# CPU_board.net
KiCad netlist of a schematic drawn in EAGLE
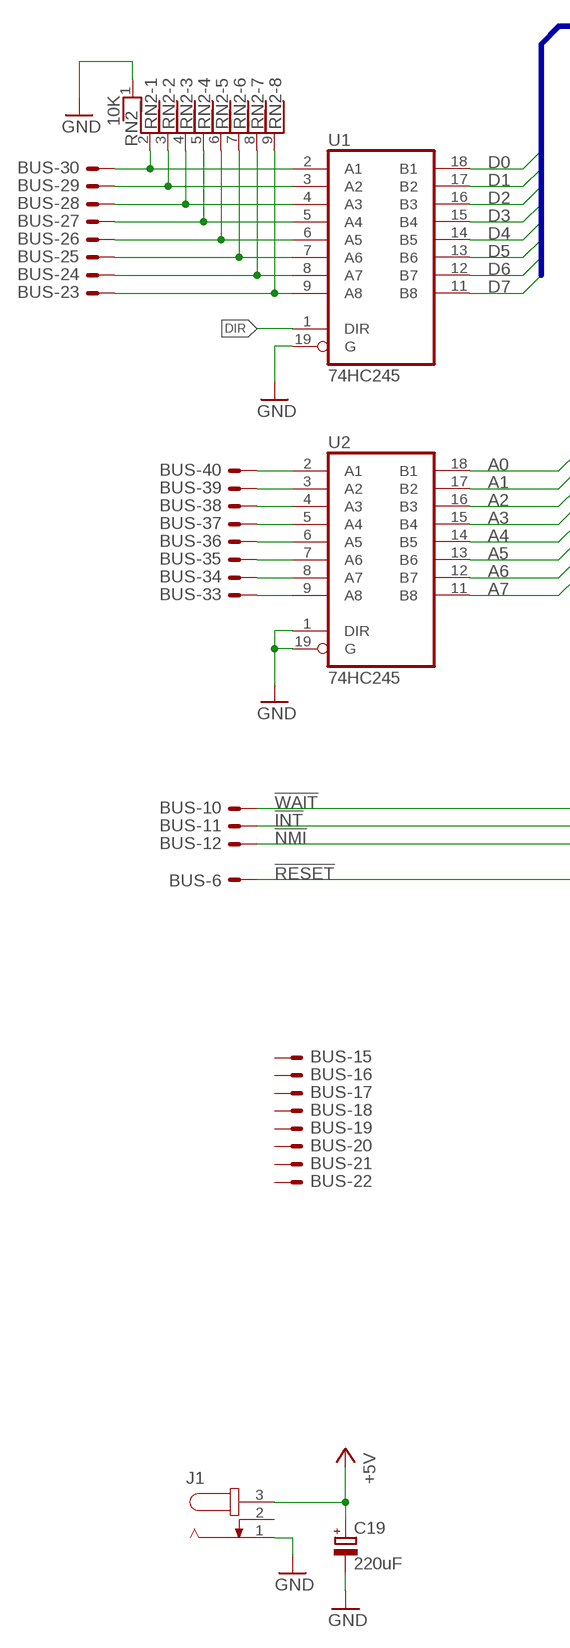
[diagram p0: schematic, sheet 1, part 1 of 2]
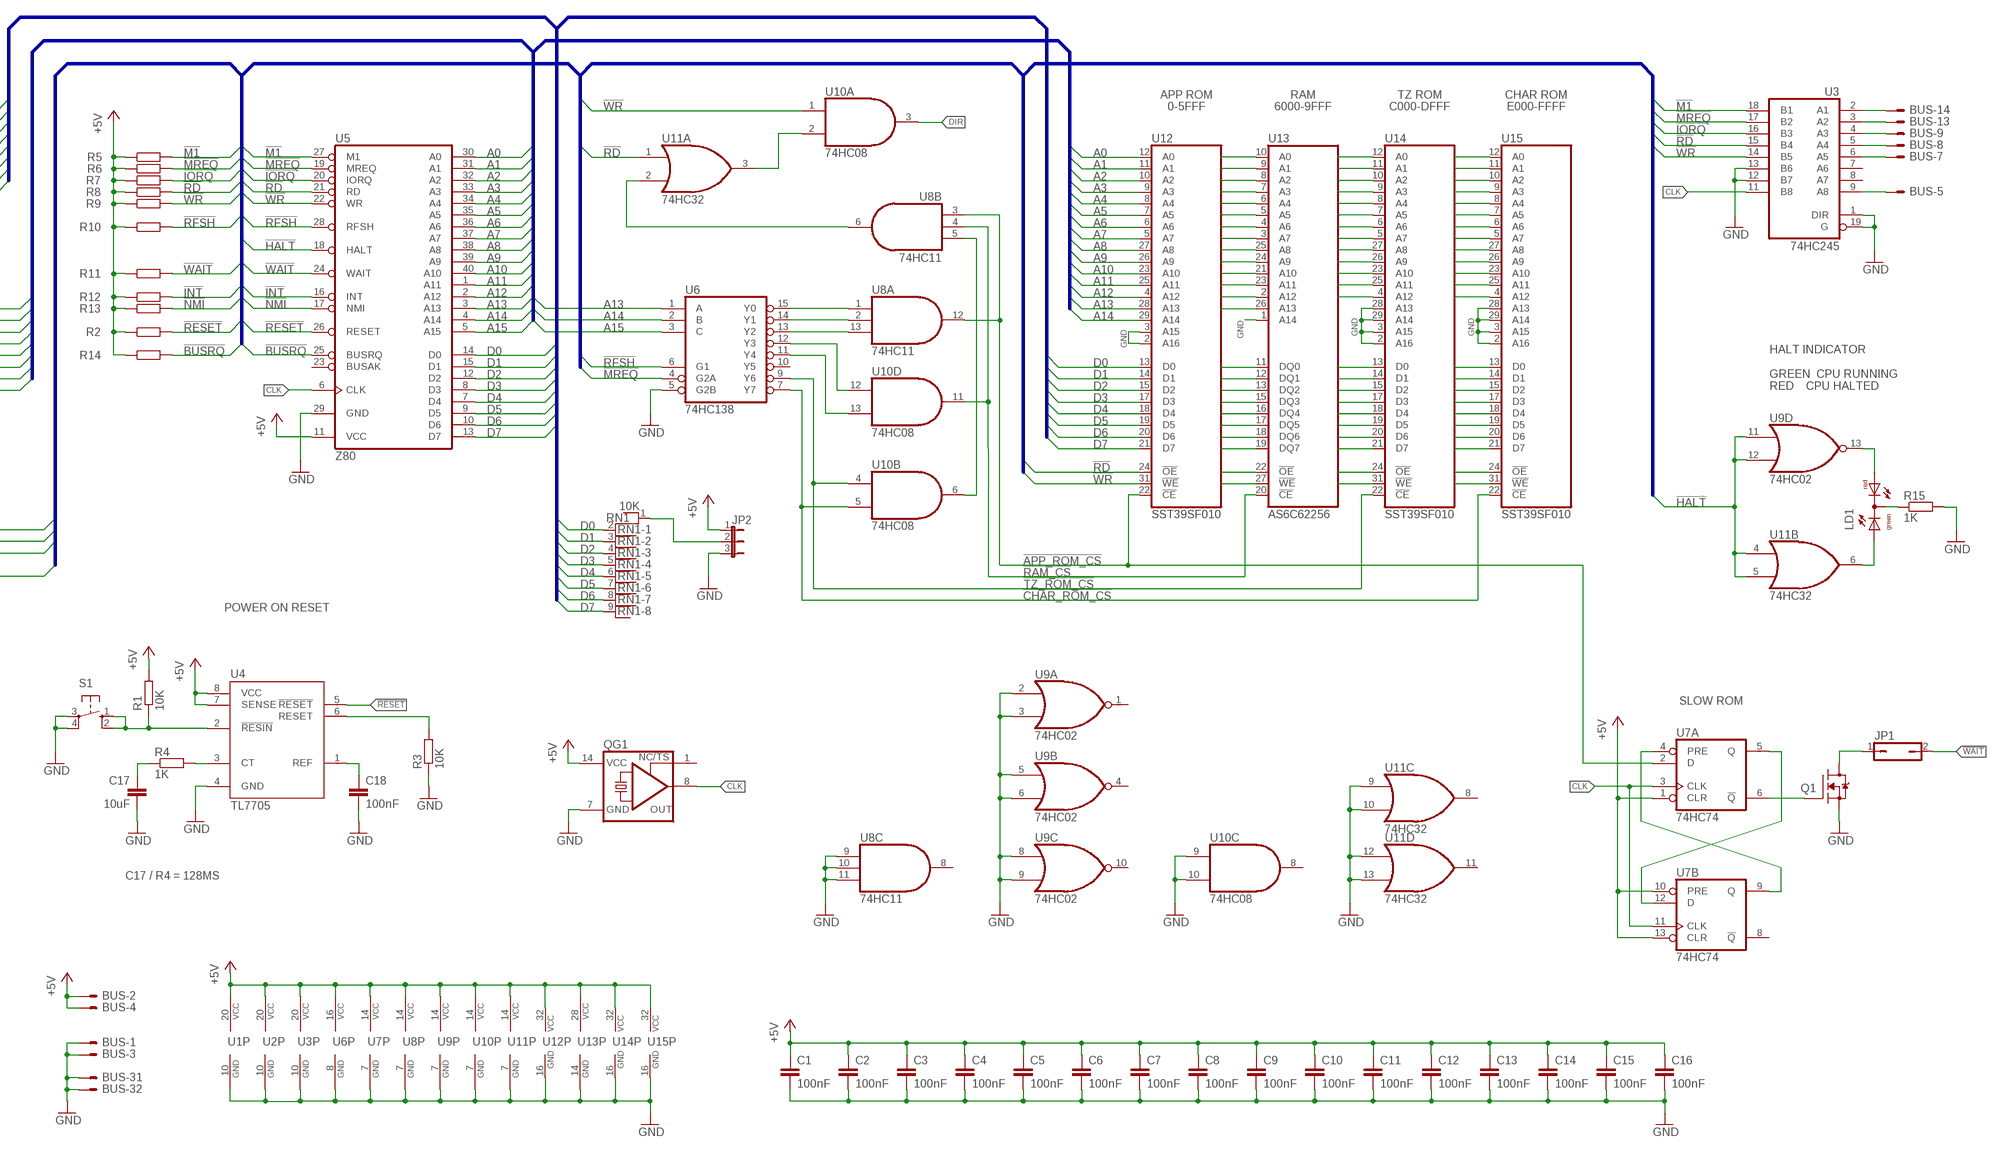
[diagram p1: schematic, sheet 1, part 2 of 2]

(export (version "E")
  (design (tool "Eeschema 10.0.6"))
  (components
    (comp (ref "BUS")
      (value "ML40E")
      (footprint "eagle-import:ML40")
      (libsource (lib "eagle-import") (part "ML40E"))
    )
    (comp (ref "C1")
      (value "100nF")
      (footprint "eagle-import:C050-025X075")
      (libsource (lib "eagle-import") (part "C-EU050-025X075"))
    )
    (comp (ref "C2")
      (value "100nF")
      (footprint "eagle-import:C050-025X075")
      (libsource (lib "eagle-import") (part "C-EU050-025X075"))
    )
    (comp (ref "C3")
      (value "100nF")
      (footprint "eagle-import:C050-025X075")
      (libsource (lib "eagle-import") (part "C-EU050-025X075"))
    )
    (comp (ref "C4")
      (value "100nF")
      (footprint "eagle-import:C050-025X075")
      (libsource (lib "eagle-import") (part "C-EU050-025X075"))
    )
    (comp (ref "C5")
      (value "100nF")
      (footprint "eagle-import:C050-025X075")
      (libsource (lib "eagle-import") (part "C-EU050-025X075"))
    )
    (comp (ref "C6")
      (value "100nF")
      (footprint "eagle-import:C050-025X075")
      (libsource (lib "eagle-import") (part "C-EU050-025X075"))
    )
    (comp (ref "C7")
      (value "100nF")
      (footprint "eagle-import:C050-025X075")
      (libsource (lib "eagle-import") (part "C-EU050-025X075"))
    )
    (comp (ref "C8")
      (value "100nF")
      (footprint "eagle-import:C050-025X075")
      (libsource (lib "eagle-import") (part "C-EU050-025X075"))
    )
    (comp (ref "C9")
      (value "100nF")
      (footprint "eagle-import:C050-025X075")
      (libsource (lib "eagle-import") (part "C-EU050-025X075"))
    )
    (comp (ref "C10")
      (value "100nF")
      (footprint "eagle-import:C050-025X075")
      (libsource (lib "eagle-import") (part "C-EU050-025X075"))
    )
    (comp (ref "C11")
      (value "100nF")
      (footprint "eagle-import:C050-025X075")
      (libsource (lib "eagle-import") (part "C-EU050-025X075"))
    )
    (comp (ref "C12")
      (value "100nF")
      (footprint "eagle-import:C050-025X075")
      (libsource (lib "eagle-import") (part "C-EU050-025X075"))
    )
    (comp (ref "C13")
      (value "100nF")
      (footprint "eagle-import:C050-025X075")
      (libsource (lib "eagle-import") (part "C-EU050-025X075"))
    )
    (comp (ref "C14")
      (value "100nF")
      (footprint "eagle-import:C050-025X075")
      (libsource (lib "eagle-import") (part "C-EU050-025X075"))
    )
    (comp (ref "C15")
      (value "100nF")
      (footprint "eagle-import:C050-025X075")
      (libsource (lib "eagle-import") (part "C-EU050-025X075"))
    )
    (comp (ref "C16")
      (value "100nF")
      (footprint "eagle-import:C050-025X075")
      (libsource (lib "eagle-import") (part "C-EU050-025X075"))
    )
    (comp (ref "C17")
      (value "10uF")
      (footprint "eagle-import:C050-025X075")
      (libsource (lib "eagle-import") (part "C-EU050-025X075"))
    )
    (comp (ref "C18")
      (value "100nF")
      (footprint "eagle-import:C050-025X075")
      (libsource (lib "eagle-import") (part "C-EU050-025X075"))
    )
    (comp (ref "C19")
      (value "220uF")
      (footprint "eagle-import:E3,5-8")
      (libsource (lib "eagle-import") (part "CPOL-EUE3.5-8"))
    )
    (comp (ref "J1")
      (value "JACK-PLUG0")
      (footprint "eagle-import:SPC4077")
      (libsource (lib "eagle-import") (part "JACK-PLUG0"))
    )
    (comp (ref "JP1")
      (value "JP1Q")
      (footprint "eagle-import:JP1")
      (libsource (lib "eagle-import") (part "JP1Q"))
    )
    (comp (ref "JP2")
      (value "JP2E")
      (footprint "eagle-import:JP2")
      (libsource (lib "eagle-import") (part "JP2E"))
    )
    (comp (ref "LD1")
      (value "DUOLED-RG-C")
      (footprint "eagle-import:DUOLED-C-5MM")
      (libsource (lib "eagle-import") (part "DUOLED-RG-C"))
    )
    (comp (ref "Q1")
      (value "2N7000")
      (footprint "eagle-import:TO-92-FORMED")
      (libsource (lib "eagle-import") (part "2N7000"))
    )
    (comp (ref "QG1")
      (value "XO-14")
      (footprint "eagle-import:DIL14S")
      (libsource (lib "eagle-import") (part "XO-14"))
    )
    (comp (ref "R1")
      (value "10K")
      (footprint "eagle-import:0207_10")
      (libsource (lib "eagle-import") (part "R-EU_0207/10"))
    )
    (comp (ref "R2")
      (value "10K")
      (footprint "eagle-import:0207_10")
      (libsource (lib "eagle-import") (part "R-EU_0207/10"))
    )
    (comp (ref "R3")
      (value "10K")
      (footprint "eagle-import:0207_10")
      (libsource (lib "eagle-import") (part "R-EU_0207/10"))
    )
    (comp (ref "R4")
      (value "1K")
      (footprint "eagle-import:0207_10")
      (libsource (lib "eagle-import") (part "R-EU_0207/10"))
    )
    (comp (ref "R5")
      (value "R-EU_0207/10")
      (footprint "eagle-import:0207_10")
      (libsource (lib "eagle-import") (part "R-EU_0207/10"))
    )
    (comp (ref "R6")
      (value "R-EU_0207/10")
      (footprint "eagle-import:0207_10")
      (libsource (lib "eagle-import") (part "R-EU_0207/10"))
    )
    (comp (ref "R7")
      (value "R-EU_0207/10")
      (footprint "eagle-import:0207_10")
      (libsource (lib "eagle-import") (part "R-EU_0207/10"))
    )
    (comp (ref "R8")
      (value "R-EU_0207/10")
      (footprint "eagle-import:0207_10")
      (libsource (lib "eagle-import") (part "R-EU_0207/10"))
    )
    (comp (ref "R9")
      (value "R-EU_0207/10")
      (footprint "eagle-import:0207_10")
      (libsource (lib "eagle-import") (part "R-EU_0207/10"))
    )
    (comp (ref "R10")
      (value "R-EU_0207/10")
      (footprint "eagle-import:0207_10")
      (libsource (lib "eagle-import") (part "R-EU_0207/10"))
    )
    (comp (ref "R11")
      (value "R-EU_0207/10")
      (footprint "eagle-import:0207_10")
      (libsource (lib "eagle-import") (part "R-EU_0207/10"))
    )
    (comp (ref "R12")
      (value "R-EU_0207/10")
      (footprint "eagle-import:0207_10")
      (libsource (lib "eagle-import") (part "R-EU_0207/10"))
    )
    (comp (ref "R13")
      (value "R-EU_0207/10")
      (footprint "eagle-import:0207_10")
      (libsource (lib "eagle-import") (part "R-EU_0207/10"))
    )
    (comp (ref "R14")
      (value "R-EU_0207/10")
      (footprint "eagle-import:0207_10")
      (libsource (lib "eagle-import") (part "R-EU_0207/10"))
    )
    (comp (ref "R15")
      (value "1K")
      (footprint "eagle-import:0207_10")
      (libsource (lib "eagle-import") (part "R-EU_0207/10"))
    )
    (comp (ref "RN1")
      (value "10K")
      (footprint "eagle-import:RN-9")
      (libsource (lib "eagle-import") (part "RNX8"))
    )
    (comp (ref "RN2")
      (value "10K")
      (footprint "eagle-import:RN-9")
      (libsource (lib "eagle-import") (part "RNX8"))
    )
    (comp (ref "S1")
      (value "10-XX")
      (footprint "eagle-import:B3F-10XX")
      (fields (field (name "MPN") "B3F-1000"))
      (libsource (lib "eagle-import") (part "10-XX"))
    )
    (comp (ref "U1")
      (value "74HC245")
      (footprint "eagle-import:DIL20")
      (libsource (lib "eagle-import") (part "74245NLS"))
    )
    (comp (ref "U2")
      (value "74HC245")
      (footprint "eagle-import:DIL20")
      (libsource (lib "eagle-import") (part "74245NLS"))
    )
    (comp (ref "U3")
      (value "74HC245")
      (footprint "eagle-import:DIL20")
      (libsource (lib "eagle-import") (part "74245NLS"))
    )
    (comp (ref "U4")
      (value "TL7705")
      (footprint "eagle-import:DIL08")
      (libsource (lib "eagle-import") (part "TL77XXA"))
    )
    (comp (ref "U5")
      (value "Z80")
      (footprint "eagle-import:DIL40")
      (libsource (lib "eagle-import") (part "Z80CPU"))
    )
    (comp (ref "U6")
      (value "74HC138")
      (footprint "eagle-import:DIL16")
      (libsource (lib "eagle-import") (part "74138NLS"))
    )
    (comp (ref "U7")
      (value "74HC74")
      (footprint "eagle-import:DIL14")
      (libsource (lib "eagle-import") (part "7474NLS"))
    )
    (comp (ref "U8")
      (value "74HC11")
      (footprint "eagle-import:DIL14")
      (libsource (lib "eagle-import") (part "7411NLS"))
    )
    (comp (ref "U9")
      (value "74HC02")
      (footprint "eagle-import:DIL14")
      (libsource (lib "eagle-import") (part "7402NLS"))
    )
    (comp (ref "U10")
      (value "74HC08")
      (footprint "eagle-import:DIL14")
      (libsource (lib "eagle-import") (part "7408NLS"))
    )
    (comp (ref "U11")
      (value "74HC32")
      (footprint "eagle-import:DIL14")
      (libsource (lib "eagle-import") (part "7432NLS"))
    )
    (comp (ref "U12")
      (value "SST39SF010")
      (footprint "eagle-import:DIL32")
      (libsource (lib "eagle-import") (part "SST39SF010P"))
    )
    (comp (ref "U13")
      (value "AS6C62256")
      (footprint "eagle-import:DIL28-6")
      (libsource (lib "eagle-import") (part "AS6C62256-55PCN"))
    )
    (comp (ref "U14")
      (value "SST39SF010")
      (footprint "eagle-import:PLCC-SR32")
      (libsource (lib "eagle-import") (part "SST39SF010NS"))
    )
    (comp (ref "U15")
      (value "SST39SF010")
      (footprint "eagle-import:PLCC-SR32")
      (libsource (lib "eagle-import") (part "SST39SF010NS"))
    )
  )
  (nets
    (net (code "18") (name "+5V") (class "Default")
      (node (ref "BUS") (pin "2") (pinfunction "S_2") (pintype "passive"))
      (node (ref "BUS") (pin "4") (pinfunction "S_4") (pintype "passive"))
      (node (ref "C1") (pin "1") (pinfunction "1_1") (pintype "passive"))
      (node (ref "C10") (pin "1") (pinfunction "1_1") (pintype "passive"))
      (node (ref "C11") (pin "1") (pinfunction "1_1") (pintype "passive"))
      (node (ref "C12") (pin "1") (pinfunction "1_1") (pintype "passive"))
      (node (ref "C13") (pin "1") (pinfunction "1_1") (pintype "passive"))
      (node (ref "C14") (pin "1") (pinfunction "1_1") (pintype "passive"))
      (node (ref "C15") (pin "1") (pinfunction "1_1") (pintype "passive"))
      (node (ref "C16") (pin "1") (pinfunction "1_1") (pintype "passive"))
      (node (ref "C19") (pin "+") (pinfunction "+_+") (pintype "passive"))
      (node (ref "C2") (pin "1") (pinfunction "1_1") (pintype "passive"))
      (node (ref "C3") (pin "1") (pinfunction "1_1") (pintype "passive"))
      (node (ref "C4") (pin "1") (pinfunction "1_1") (pintype "passive"))
      (node (ref "C5") (pin "1") (pinfunction "1_1") (pintype "passive"))
      (node (ref "C6") (pin "1") (pinfunction "1_1") (pintype "passive"))
      (node (ref "C7") (pin "1") (pinfunction "1_1") (pintype "passive"))
      (node (ref "C8") (pin "1") (pinfunction "1_1") (pintype "passive"))
      (node (ref "C9") (pin "1") (pinfunction "1_1") (pintype "passive"))
      (node (ref "J1") (pin "3") (pinfunction "3_3") (pintype "passive"))
      (node (ref "JP2") (pin "1") (pinfunction "1_1") (pintype "passive"))
      (node (ref "QG1") (pin "14") (pinfunction "VCC_14") (pintype "power_in"))
      (node (ref "R1") (pin "2") (pinfunction "2_2") (pintype "passive"))
      (node (ref "R10") (pin "1") (pinfunction "1_1") (pintype "passive"))
      (node (ref "R11") (pin "1") (pinfunction "1_1") (pintype "passive"))
      (node (ref "R12") (pin "1") (pinfunction "1_1") (pintype "passive"))
      (node (ref "R13") (pin "1") (pinfunction "1_1") (pintype "passive"))
      (node (ref "R14") (pin "1") (pinfunction "1_1") (pintype "passive"))
      (node (ref "R2") (pin "1") (pinfunction "1_1") (pintype "passive"))
      (node (ref "R5") (pin "1") (pinfunction "1_1") (pintype "passive"))
      (node (ref "R6") (pin "1") (pinfunction "1_1") (pintype "passive"))
      (node (ref "R7") (pin "1") (pinfunction "1_1") (pintype "passive"))
      (node (ref "R8") (pin "1") (pinfunction "1_1") (pintype "passive"))
      (node (ref "R9") (pin "1") (pinfunction "1_1") (pintype "passive"))
      (node (ref "U1") (pin "20") (pinfunction "VCC_20") (pintype "power_in"))
      (node (ref "U10") (pin "14") (pinfunction "VCC_14") (pintype "power_in"))
      (node (ref "U11") (pin "14") (pinfunction "VCC_14") (pintype "power_in"))
      (node (ref "U12") (pin "32") (pinfunction "VCC_32") (pintype "power_in"))
      (node (ref "U13") (pin "28") (pinfunction "VCC_28") (pintype "power_in"))
      (node (ref "U14") (pin "32") (pinfunction "VCC_32") (pintype "power_in"))
      (node (ref "U15") (pin "32") (pinfunction "VCC_32") (pintype "power_in"))
      (node (ref "U2") (pin "20") (pinfunction "VCC_20") (pintype "power_in"))
      (node (ref "U3") (pin "20") (pinfunction "VCC_20") (pintype "power_in"))
      (node (ref "U4") (pin "7") (pinfunction "SENSE_7") (pintype "input"))
      (node (ref "U4") (pin "8") (pinfunction "VCC_8") (pintype "power_in"))
      (node (ref "U5") (pin "11") (pinfunction "VCC_11") (pintype "power_in"))
      (node (ref "U6") (pin "16") (pinfunction "VCC_16") (pintype "power_in"))
      (node (ref "U7") (pin "1") (pinfunction "CLR_1") (pintype "input"))
      (node (ref "U7") (pin "10") (pinfunction "PRE_10") (pintype "input"))
      (node (ref "U7") (pin "13") (pinfunction "CLR_13") (pintype "input"))
      (node (ref "U7") (pin "14") (pinfunction "VCC_14") (pintype "power_in"))
      (node (ref "U8") (pin "14") (pinfunction "VCC_14") (pintype "power_in"))
      (node (ref "U9") (pin "14") (pinfunction "VCC_14") (pintype "power_in"))
    )
    (net (code "21") (name "A0") (class "Default")
      (node (ref "U12") (pin "12") (pinfunction "A0_12") (pintype "input"))
      (node (ref "U13") (pin "10") (pinfunction "A0_10") (pintype "input"))
      (node (ref "U14") (pin "12") (pinfunction "A0_12") (pintype "input"))
      (node (ref "U15") (pin "12") (pinfunction "A0_12") (pintype "input"))
      (node (ref "U2") (pin "18") (pinfunction "B1_18") (pintype "bidirectional"))
      (node (ref "U5") (pin "30") (pinfunction "A0_30") (pintype "output"))
    )
    (net (code "22") (name "A1") (class "Default")
      (node (ref "U12") (pin "11") (pinfunction "A1_11") (pintype "input"))
      (node (ref "U13") (pin "9") (pinfunction "A1_9") (pintype "input"))
      (node (ref "U14") (pin "11") (pinfunction "A1_11") (pintype "input"))
      (node (ref "U15") (pin "11") (pinfunction "A1_11") (pintype "input"))
      (node (ref "U2") (pin "17") (pinfunction "B2_17") (pintype "bidirectional"))
      (node (ref "U5") (pin "31") (pinfunction "A1_31") (pintype "output"))
    )
    (net (code "23") (name "A2") (class "Default")
      (node (ref "U12") (pin "10") (pinfunction "A2_10") (pintype "input"))
      (node (ref "U13") (pin "8") (pinfunction "A2_8") (pintype "input"))
      (node (ref "U14") (pin "10") (pinfunction "A2_10") (pintype "input"))
      (node (ref "U15") (pin "10") (pinfunction "A2_10") (pintype "input"))
      (node (ref "U2") (pin "16") (pinfunction "B3_16") (pintype "bidirectional"))
      (node (ref "U5") (pin "32") (pinfunction "A2_32") (pintype "output"))
    )
    (net (code "24") (name "A3") (class "Default")
      (node (ref "U12") (pin "9") (pinfunction "A3_9") (pintype "input"))
      (node (ref "U13") (pin "7") (pinfunction "A3_7") (pintype "input"))
      (node (ref "U14") (pin "9") (pinfunction "A3_9") (pintype "input"))
      (node (ref "U15") (pin "9") (pinfunction "A3_9") (pintype "input"))
      (node (ref "U2") (pin "15") (pinfunction "B4_15") (pintype "bidirectional"))
      (node (ref "U5") (pin "33") (pinfunction "A3_33") (pintype "output"))
    )
    (net (code "25") (name "A4") (class "Default")
      (node (ref "U12") (pin "8") (pinfunction "A4_8") (pintype "input"))
      (node (ref "U13") (pin "6") (pinfunction "A4_6") (pintype "input"))
      (node (ref "U14") (pin "8") (pinfunction "A4_8") (pintype "input"))
      (node (ref "U15") (pin "8") (pinfunction "A4_8") (pintype "input"))
      (node (ref "U2") (pin "14") (pinfunction "B5_14") (pintype "bidirectional"))
      (node (ref "U5") (pin "34") (pinfunction "A4_34") (pintype "output"))
    )
    (net (code "26") (name "A5") (class "Default")
      (node (ref "U12") (pin "7") (pinfunction "A5_7") (pintype "input"))
      (node (ref "U13") (pin "5") (pinfunction "A5_5") (pintype "input"))
      (node (ref "U14") (pin "7") (pinfunction "A5_7") (pintype "input"))
      (node (ref "U15") (pin "7") (pinfunction "A5_7") (pintype "input"))
      (node (ref "U2") (pin "13") (pinfunction "B6_13") (pintype "bidirectional"))
      (node (ref "U5") (pin "35") (pinfunction "A5_35") (pintype "output"))
    )
    (net (code "27") (name "A6") (class "Default")
      (node (ref "U12") (pin "6") (pinfunction "A6_6") (pintype "input"))
      (node (ref "U13") (pin "4") (pinfunction "A6_4") (pintype "input"))
      (node (ref "U14") (pin "6") (pinfunction "A6_6") (pintype "input"))
      (node (ref "U15") (pin "6") (pinfunction "A6_6") (pintype "input"))
      (node (ref "U2") (pin "12") (pinfunction "B7_12") (pintype "bidirectional"))
      (node (ref "U5") (pin "36") (pinfunction "A6_36") (pintype "output"))
    )
    (net (code "28") (name "A7") (class "Default")
      (node (ref "U12") (pin "5") (pinfunction "A7_5") (pintype "input"))
      (node (ref "U13") (pin "3") (pinfunction "A7_3") (pintype "input"))
      (node (ref "U14") (pin "5") (pinfunction "A7_5") (pintype "input"))
      (node (ref "U15") (pin "5") (pinfunction "A7_5") (pintype "input"))
      (node (ref "U2") (pin "11") (pinfunction "B8_11") (pintype "bidirectional"))
      (node (ref "U5") (pin "37") (pinfunction "A7_37") (pintype "output"))
    )
    (net (code "29") (name "A8") (class "Default")
      (node (ref "U12") (pin "27") (pinfunction "A8_27") (pintype "input"))
      (node (ref "U13") (pin "25") (pinfunction "A8_25") (pintype "input"))
      (node (ref "U14") (pin "27") (pinfunction "A8_27") (pintype "input"))
      (node (ref "U15") (pin "27") (pinfunction "A8_27") (pintype "input"))
      (node (ref "U5") (pin "38") (pinfunction "A8_38") (pintype "output"))
    )
    (net (code "30") (name "A9") (class "Default")
      (node (ref "U12") (pin "26") (pinfunction "A9_26") (pintype "input"))
      (node (ref "U13") (pin "24") (pinfunction "A9_24") (pintype "input"))
      (node (ref "U14") (pin "26") (pinfunction "A9_26") (pintype "input"))
      (node (ref "U15") (pin "26") (pinfunction "A9_26") (pintype "input"))
      (node (ref "U5") (pin "39") (pinfunction "A9_39") (pintype "output"))
    )
    (net (code "31") (name "A10") (class "Default")
      (node (ref "U12") (pin "23") (pinfunction "A10_23") (pintype "input"))
      (node (ref "U13") (pin "21") (pinfunction "A10_21") (pintype "input"))
      (node (ref "U14") (pin "23") (pinfunction "A10_23") (pintype "input"))
      (node (ref "U15") (pin "23") (pinfunction "A10_23") (pintype "input"))
      (node (ref "U5") (pin "40") (pinfunction "A10_40") (pintype "output"))
    )
    (net (code "32") (name "A11") (class "Default")
      (node (ref "U12") (pin "25") (pinfunction "A11_25") (pintype "input"))
      (node (ref "U13") (pin "23") (pinfunction "A11_23") (pintype "input"))
      (node (ref "U14") (pin "25") (pinfunction "A11_25") (pintype "input"))
      (node (ref "U15") (pin "25") (pinfunction "A11_25") (pintype "input"))
      (node (ref "U5") (pin "1") (pinfunction "A11_1") (pintype "output"))
    )
    (net (code "33") (name "A12") (class "Default")
      (node (ref "U12") (pin "4") (pinfunction "A12_4") (pintype "input"))
      (node (ref "U13") (pin "2") (pinfunction "A12_2") (pintype "input"))
      (node (ref "U14") (pin "4") (pinfunction "A12_4") (pintype "input"))
      (node (ref "U15") (pin "4") (pinfunction "A12_4") (pintype "input"))
      (node (ref "U5") (pin "2") (pinfunction "A12_2") (pintype "output"))
    )
    (net (code "34") (name "A13") (class "Default")
      (node (ref "U12") (pin "28") (pinfunction "A13_28") (pintype "input"))
      (node (ref "U13") (pin "26") (pinfunction "A13_26") (pintype "input"))
      (node (ref "U5") (pin "3") (pinfunction "A13_3") (pintype "output"))
      (node (ref "U6") (pin "1") (pinfunction "A_1") (pintype "input"))
    )
    (net (code "35") (name "A14") (class "Default")
      (node (ref "U12") (pin "29") (pinfunction "A14_29") (pintype "input"))
      (node (ref "U5") (pin "4") (pinfunction "A14_4") (pintype "output"))
      (node (ref "U6") (pin "2") (pinfunction "B_2") (pintype "input"))
    )
    (net (code "36") (name "A15") (class "Default")
      (node (ref "U5") (pin "5") (pinfunction "A15_5") (pintype "output"))
      (node (ref "U6") (pin "3") (pinfunction "C_3") (pintype "input"))
    )
    (net (code "37") (name "CLK") (class "Default")
      (node (ref "QG1") (pin "8") (pinfunction "OUT_8") (pintype "output"))
      (node (ref "U3") (pin "11") (pinfunction "B8_11") (pintype "bidirectional"))
      (node (ref "U5") (pin "6") (pinfunction "CLK_6") (pintype "input"))
      (node (ref "U7") (pin "11") (pinfunction "CLK_11") (pintype "input"))
      (node (ref "U7") (pin "3") (pinfunction "CLK_3") (pintype "input"))
    )
    (net (code "38") (name "D0") (class "Default")
      (node (ref "RN1") (pin "2") (pinfunction "1_2") (pintype "passive"))
      (node (ref "U1") (pin "18") (pinfunction "B1_18") (pintype "bidirectional"))
      (node (ref "U12") (pin "13") (pinfunction "D0_13") (pintype "bidirectional"))
      (node (ref "U13") (pin "11") (pinfunction "DQ0_11") (pintype "bidirectional"))
      (node (ref "U14") (pin "13") (pinfunction "D0_13") (pintype "bidirectional"))
      (node (ref "U15") (pin "13") (pinfunction "D0_13") (pintype "bidirectional"))
      (node (ref "U5") (pin "14") (pinfunction "D0_14") (pintype "bidirectional"))
    )
    (net (code "39") (name "D1") (class "Default")
      (node (ref "RN1") (pin "3") (pinfunction "1_3") (pintype "passive"))
      (node (ref "U1") (pin "17") (pinfunction "B2_17") (pintype "bidirectional"))
      (node (ref "U12") (pin "14") (pinfunction "D1_14") (pintype "bidirectional"))
      (node (ref "U13") (pin "12") (pinfunction "DQ1_12") (pintype "bidirectional"))
      (node (ref "U14") (pin "14") (pinfunction "D1_14") (pintype "bidirectional"))
      (node (ref "U15") (pin "14") (pinfunction "D1_14") (pintype "bidirectional"))
      (node (ref "U5") (pin "15") (pinfunction "D1_15") (pintype "bidirectional"))
    )
    (net (code "40") (name "D2") (class "Default")
      (node (ref "RN1") (pin "4") (pinfunction "1_4") (pintype "passive"))
      (node (ref "U1") (pin "16") (pinfunction "B3_16") (pintype "bidirectional"))
      (node (ref "U12") (pin "15") (pinfunction "D2_15") (pintype "bidirectional"))
      (node (ref "U13") (pin "13") (pinfunction "DQ2_13") (pintype "bidirectional"))
      (node (ref "U14") (pin "15") (pinfunction "D2_15") (pintype "bidirectional"))
      (node (ref "U15") (pin "15") (pinfunction "D2_15") (pintype "bidirectional"))
      (node (ref "U5") (pin "12") (pinfunction "D2_12") (pintype "bidirectional"))
    )
    (net (code "41") (name "D3") (class "Default")
      (node (ref "RN1") (pin "5") (pinfunction "1_5") (pintype "passive"))
      (node (ref "U1") (pin "15") (pinfunction "B4_15") (pintype "bidirectional"))
      (node (ref "U12") (pin "17") (pinfunction "D3_17") (pintype "bidirectional"))
      (node (ref "U13") (pin "15") (pinfunction "DQ3_15") (pintype "bidirectional"))
      (node (ref "U14") (pin "17") (pinfunction "D3_17") (pintype "bidirectional"))
      (node (ref "U15") (pin "17") (pinfunction "D3_17") (pintype "bidirectional"))
      (node (ref "U5") (pin "8") (pinfunction "D3_8") (pintype "bidirectional"))
    )
    (net (code "42") (name "D4") (class "Default")
      (node (ref "RN1") (pin "6") (pinfunction "1_6") (pintype "passive"))
      (node (ref "U1") (pin "14") (pinfunction "B5_14") (pintype "bidirectional"))
      (node (ref "U12") (pin "18") (pinfunction "D4_18") (pintype "bidirectional"))
      (node (ref "U13") (pin "16") (pinfunction "DQ4_16") (pintype "bidirectional"))
      (node (ref "U14") (pin "18") (pinfunction "D4_18") (pintype "bidirectional"))
      (node (ref "U15") (pin "18") (pinfunction "D4_18") (pintype "bidirectional"))
      (node (ref "U5") (pin "7") (pinfunction "D4_7") (pintype "bidirectional"))
    )
    (net (code "43") (name "D5") (class "Default")
      (node (ref "RN1") (pin "7") (pinfunction "1_7") (pintype "passive"))
      (node (ref "U1") (pin "13") (pinfunction "B6_13") (pintype "bidirectional"))
      (node (ref "U12") (pin "19") (pinfunction "D5_19") (pintype "bidirectional"))
      (node (ref "U13") (pin "17") (pinfunction "DQ5_17") (pintype "bidirectional"))
      (node (ref "U14") (pin "19") (pinfunction "D5_19") (pintype "bidirectional"))
      (node (ref "U15") (pin "19") (pinfunction "D5_19") (pintype "bidirectional"))
      (node (ref "U5") (pin "9") (pinfunction "D5_9") (pintype "bidirectional"))
    )
    (net (code "44") (name "D6") (class "Default")
      (node (ref "RN1") (pin "8") (pinfunction "1_8") (pintype "passive"))
      (node (ref "U1") (pin "12") (pinfunction "B7_12") (pintype "bidirectional"))
      (node (ref "U12") (pin "20") (pinfunction "D6_20") (pintype "bidirectional"))
      (node (ref "U13") (pin "18") (pinfunction "DQ6_18") (pintype "bidirectional"))
      (node (ref "U14") (pin "20") (pinfunction "D6_20") (pintype "bidirectional"))
      (node (ref "U15") (pin "20") (pinfunction "D6_20") (pintype "bidirectional"))
      (node (ref "U5") (pin "10") (pinfunction "D6_10") (pintype "bidirectional"))
    )
    (net (code "45") (name "D7") (class "Default")
      (node (ref "RN1") (pin "9") (pinfunction "1_9") (pintype "passive"))
      (node (ref "U1") (pin "11") (pinfunction "B8_11") (pintype "bidirectional"))
      (node (ref "U12") (pin "21") (pinfunction "D7_21") (pintype "bidirectional"))
      (node (ref "U13") (pin "19") (pinfunction "DQ7_19") (pintype "bidirectional"))
      (node (ref "U14") (pin "21") (pinfunction "D7_21") (pintype "bidirectional"))
      (node (ref "U15") (pin "21") (pinfunction "D7_21") (pintype "bidirectional"))
      (node (ref "U5") (pin "13") (pinfunction "D7_13") (pintype "bidirectional"))
    )
    (net (code "46") (name "DIR") (class "Default")
      (node (ref "U1") (pin "1") (pinfunction "DIR_1") (pintype "input"))
      (node (ref "U10") (pin "3") (pinfunction "O_3") (pintype "output"))
    )
    (net (code "47") (name "GND") (class "Default")
      (node (ref "BUS") (pin "1") (pinfunction "S_1") (pintype "passive"))
      (node (ref "BUS") (pin "3") (pinfunction "S_3") (pintype "passive"))
      (node (ref "BUS") (pin "31") (pinfunction "S_31") (pintype "passive"))
      (node (ref "BUS") (pin "32") (pinfunction "S_32") (pintype "passive"))
      (node (ref "C1") (pin "2") (pinfunction "2_2") (pintype "passive"))
      (node (ref "C10") (pin "2") (pinfunction "2_2") (pintype "passive"))
      (node (ref "C11") (pin "2") (pinfunction "2_2") (pintype "passive"))
      (node (ref "C12") (pin "2") (pinfunction "2_2") (pintype "passive"))
      (node (ref "C13") (pin "2") (pinfunction "2_2") (pintype "passive"))
      (node (ref "C14") (pin "2") (pinfunction "2_2") (pintype "passive"))
      (node (ref "C15") (pin "2") (pinfunction "2_2") (pintype "passive"))
      (node (ref "C16") (pin "2") (pinfunction "2_2") (pintype "passive"))
      (node (ref "C17") (pin "2") (pinfunction "2_2") (pintype "passive"))
      (node (ref "C18") (pin "2") (pinfunction "2_2") (pintype "passive"))
      (node (ref "C19") (pin "-") (pinfunction "-_-") (pintype "passive"))
      (node (ref "C2") (pin "2") (pinfunction "2_2") (pintype "passive"))
      (node (ref "C3") (pin "2") (pinfunction "2_2") (pintype "passive"))
      (node (ref "C4") (pin "2") (pinfunction "2_2") (pintype "passive"))
      (node (ref "C5") (pin "2") (pinfunction "2_2") (pintype "passive"))
      (node (ref "C6") (pin "2") (pinfunction "2_2") (pintype "passive"))
      (node (ref "C7") (pin "2") (pinfunction "2_2") (pintype "passive"))
      (node (ref "C8") (pin "2") (pinfunction "2_2") (pintype "passive"))
      (node (ref "C9") (pin "2") (pinfunction "2_2") (pintype "passive"))
      (node (ref "J1") (pin "1") (pinfunction "1_1") (pintype "passive"))
      (node (ref "JP2") (pin "3") (pinfunction "3_3") (pintype "passive"))
      (node (ref "Q1") (pin "1") (pinfunction "S_1") (pintype "passive"))
      (node (ref "QG1") (pin "7") (pinfunction "GND_7") (pintype "power_in"))
      (node (ref "R15") (pin "2") (pinfunction "2_2") (pintype "passive"))
      (node (ref "R3") (pin "1") (pinfunction "1_1") (pintype "passive"))
      (node (ref "RN2") (pin "1") (pinfunction "1_1") (pintype "passive"))
      (node (ref "S1") (pin "3") (pinfunction "P_3") (pintype "passive"))
      (node (ref "S1") (pin "4") (pinfunction "P1_4") (pintype "passive"))
      (node (ref "U1") (pin "10") (pinfunction "GND_10") (pintype "power_in"))
      (node (ref "U1") (pin "19") (pinfunction "G_19") (pintype "input"))
      (node (ref "U10") (pin "10") (pinfunction "I1_10") (pintype "input"))
      (node (ref "U10") (pin "7") (pinfunction "GND_7") (pintype "power_in"))
      (node (ref "U10") (pin "9") (pinfunction "I0_9") (pintype "input"))
      (node (ref "U11") (pin "10") (pinfunction "I1_10") (pintype "input"))
      (node (ref "U11") (pin "12") (pinfunction "I0_12") (pintype "input"))
      (node (ref "U11") (pin "13") (pinfunction "I1_13") (pintype "input"))
      (node (ref "U11") (pin "7") (pinfunction "GND_7") (pintype "power_in"))
      (node (ref "U11") (pin "9") (pinfunction "I0_9") (pintype "input"))
      (node (ref "U12") (pin "16") (pinfunction "GND_16") (pintype "power_in"))
      (node (ref "U12") (pin "2") (pinfunction "A16_2") (pintype "input"))
      (node (ref "U12") (pin "3") (pinfunction "A15_3") (pintype "input"))
      (node (ref "U13") (pin "1") (pinfunction "A14_1") (pintype "input"))
      (node (ref "U13") (pin "14") (pinfunction "GND_14") (pintype "power_in"))
      (node (ref "U14") (pin "16") (pinfunction "GND_16") (pintype "power_in"))
      (node (ref "U14") (pin "2") (pinfunction "A16_2") (pintype "input"))
      (node (ref "U14") (pin "28") (pinfunction "A13_28") (pintype "input"))
      (node (ref "U14") (pin "29") (pinfunction "A14_29") (pintype "input"))
      (node (ref "U14") (pin "3") (pinfunction "A15_3") (pintype "input"))
      (node (ref "U15") (pin "16") (pinfunction "GND_16") (pintype "power_in"))
      (node (ref "U15") (pin "2") (pinfunction "A16_2") (pintype "input"))
      (node (ref "U15") (pin "28") (pinfunction "A13_28") (pintype "input"))
      (node (ref "U15") (pin "29") (pinfunction "A14_29") (pintype "input"))
      (node (ref "U15") (pin "3") (pinfunction "A15_3") (pintype "input"))
      (node (ref "U2") (pin "1") (pinfunction "DIR_1") (pintype "input"))
      (node (ref "U2") (pin "10") (pinfunction "GND_10") (pintype "power_in"))
      (node (ref "U2") (pin "19") (pinfunction "G_19") (pintype "input"))
      (node (ref "U3") (pin "1") (pinfunction "DIR_1") (pintype "input"))
      (node (ref "U3") (pin "10") (pinfunction "GND_10") (pintype "power_in"))
      (node (ref "U3") (pin "12") (pinfunction "B7_12") (pintype "bidirectional"))
      (node (ref "U3") (pin "13") (pinfunction "B6_13") (pintype "bidirectional"))
      (node (ref "U3") (pin "19") (pinfunction "G_19") (pintype "input"))
      (node (ref "U4") (pin "4") (pinfunction "GND_4") (pintype "power_in"))
      (node (ref "U5") (pin "29") (pinfunction "GND_29") (pintype "power_in"))
      (node (ref "U6") (pin "5") (pinfunction "G2B_5") (pintype "input"))
      (node (ref "U6") (pin "8") (pinfunction "GND_8") (pintype "power_in"))
      (node (ref "U7") (pin "7") (pinfunction "GND_7") (pintype "power_in"))
      (node (ref "U8") (pin "10") (pinfunction "I1_10") (pintype "input"))
      (node (ref "U8") (pin "11") (pinfunction "I2_11") (pintype "input"))
      (node (ref "U8") (pin "7") (pinfunction "GND_7") (pintype "power_in"))
      (node (ref "U8") (pin "9") (pinfunction "I0_9") (pintype "input"))
      (node (ref "U9") (pin "2") (pinfunction "I0_2") (pintype "input"))
      (node (ref "U9") (pin "3") (pinfunction "I1_3") (pintype "input"))
      (node (ref "U9") (pin "5") (pinfunction "I0_5") (pintype "input"))
      (node (ref "U9") (pin "6") (pinfunction "I1_6") (pintype "input"))
      (node (ref "U9") (pin "7") (pinfunction "GND_7") (pintype "power_in"))
      (node (ref "U9") (pin "8") (pinfunction "I0_8") (pintype "input"))
      (node (ref "U9") (pin "9") (pinfunction "I1_9") (pintype "input"))
    )
    (net (code "48") (name "Net-(BUSAA-S)") (class "Default")
      (node (ref "BUS") (pin "33") (pinfunction "S_33") (pintype "passive"))
      (node (ref "U2") (pin "9") (pinfunction "A8_9") (pintype "bidirectional"))
    )
    (net (code "49") (name "Net-(BUSAB-S)") (class "Default")
      (node (ref "BUS") (pin "34") (pinfunction "S_34") (pintype "passive"))
      (node (ref "U2") (pin "8") (pinfunction "A7_8") (pintype "bidirectional"))
    )
    (net (code "50") (name "Net-(BUSAC-S)") (class "Default")
      (node (ref "BUS") (pin "35") (pinfunction "S_35") (pintype "passive"))
      (node (ref "U2") (pin "7") (pinfunction "A6_7") (pintype "bidirectional"))
    )
    (net (code "51") (name "Net-(BUSAD-S)") (class "Default")
      (node (ref "BUS") (pin "36") (pinfunction "S_36") (pintype "passive"))
      (node (ref "U2") (pin "6") (pinfunction "A5_6") (pintype "bidirectional"))
    )
    (net (code "52") (name "Net-(BUSAE-S)") (class "Default")
      (node (ref "BUS") (pin "37") (pinfunction "S_37") (pintype "passive"))
      (node (ref "U2") (pin "5") (pinfunction "A4_5") (pintype "bidirectional"))
    )
    (net (code "53") (name "Net-(BUSAF-S)") (class "Default")
      (node (ref "BUS") (pin "38") (pinfunction "S_38") (pintype "passive"))
      (node (ref "U2") (pin "4") (pinfunction "A3_4") (pintype "bidirectional"))
    )
    (net (code "54") (name "Net-(BUSAG-S)") (class "Default")
      (node (ref "BUS") (pin "39") (pinfunction "S_39") (pintype "passive"))
      (node (ref "U2") (pin "3") (pinfunction "A2_3") (pintype "bidirectional"))
    )
    (net (code "55") (name "Net-(BUSAI-S)") (class "Default")
      (node (ref "BUS") (pin "40") (pinfunction "S_40") (pintype "passive"))
      (node (ref "U2") (pin "2") (pinfunction "A1_2") (pintype "bidirectional"))
    )
    (net (code "56") (name "Net-(BUSAJ-S)") (class "Default")
      (node (ref "BUS") (pin "5") (pinfunction "S_5") (pintype "passive"))
      (node (ref "U3") (pin "9") (pinfunction "A8_9") (pintype "bidirectional"))
    )
    (net (code "57") (name "Net-(BUSAL-S)") (class "Default")
      (node (ref "BUS") (pin "7") (pinfunction "S_7") (pintype "passive"))
      (node (ref "U3") (pin "6") (pinfunction "A5_6") (pintype "bidirectional"))
    )
    (net (code "58") (name "Net-(BUSAM-S)") (class "Default")
      (node (ref "BUS") (pin "8") (pinfunction "S_8") (pintype "passive"))
      (node (ref "U3") (pin "5") (pinfunction "A4_5") (pintype "bidirectional"))
    )
    (net (code "59") (name "Net-(BUSAN-S)") (class "Default")
      (node (ref "BUS") (pin "9") (pinfunction "S_9") (pintype "passive"))
      (node (ref "U3") (pin "4") (pinfunction "A3_4") (pintype "bidirectional"))
    )
    (net (code "60") (name "Net-(BUSE-S)") (class "Default")
      (node (ref "BUS") (pin "13") (pinfunction "S_13") (pintype "passive"))
      (node (ref "U3") (pin "3") (pinfunction "A2_3") (pintype "bidirectional"))
    )
    (net (code "61") (name "Net-(BUSF-S)") (class "Default")
      (node (ref "BUS") (pin "14") (pinfunction "S_14") (pintype "passive"))
      (node (ref "U3") (pin "2") (pinfunction "A1_2") (pintype "bidirectional"))
    )
    (net (code "62") (name "Net-(BUSP-S)") (class "Default")
      (node (ref "BUS") (pin "23") (pinfunction "S_23") (pintype "passive"))
      (node (ref "RN2") (pin "9") (pinfunction "1_9") (pintype "passive"))
      (node (ref "U1") (pin "9") (pinfunction "A8_9") (pintype "bidirectional"))
    )
    (net (code "63") (name "Net-(BUSQ-S)") (class "Default")
      (node (ref "BUS") (pin "24") (pinfunction "S_24") (pintype "passive"))
      (node (ref "RN2") (pin "8") (pinfunction "1_8") (pintype "passive"))
      (node (ref "U1") (pin "8") (pinfunction "A7_8") (pintype "bidirectional"))
    )
    (net (code "64") (name "Net-(BUSR-S)") (class "Default")
      (node (ref "BUS") (pin "25") (pinfunction "S_25") (pintype "passive"))
      (node (ref "RN2") (pin "7") (pinfunction "1_7") (pintype "passive"))
      (node (ref "U1") (pin "7") (pinfunction "A6_7") (pintype "bidirectional"))
    )
    (net (code "65") (name "Net-(BUSS-S)") (class "Default")
      (node (ref "BUS") (pin "26") (pinfunction "S_26") (pintype "passive"))
      (node (ref "RN2") (pin "6") (pinfunction "1_6") (pintype "passive"))
      (node (ref "U1") (pin "6") (pinfunction "A5_6") (pintype "bidirectional"))
    )
    (net (code "66") (name "Net-(BUST-S)") (class "Default")
      (node (ref "BUS") (pin "27") (pinfunction "S_27") (pintype "passive"))
      (node (ref "RN2") (pin "5") (pinfunction "1_5") (pintype "passive"))
      (node (ref "U1") (pin "5") (pinfunction "A4_5") (pintype "bidirectional"))
    )
    (net (code "67") (name "Net-(BUSU-S)") (class "Default")
      (node (ref "BUS") (pin "28") (pinfunction "S_28") (pintype "passive"))
      (node (ref "RN2") (pin "4") (pinfunction "1_4") (pintype "passive"))
      (node (ref "U1") (pin "4") (pinfunction "A3_4") (pintype "bidirectional"))
    )
    (net (code "68") (name "Net-(BUSV-S)") (class "Default")
      (node (ref "BUS") (pin "29") (pinfunction "S_29") (pintype "passive"))
      (node (ref "RN2") (pin "3") (pinfunction "1_3") (pintype "passive"))
      (node (ref "U1") (pin "3") (pinfunction "A2_3") (pintype "bidirectional"))
    )
    (net (code "69") (name "Net-(BUSX-S)") (class "Default")
      (node (ref "BUS") (pin "30") (pinfunction "S_30") (pintype "passive"))
      (node (ref "RN2") (pin "2") (pinfunction "1_2") (pintype "passive"))
      (node (ref "U1") (pin "2") (pinfunction "A1_2") (pintype "bidirectional"))
    )
    (net (code "70") (name "Net-(C17-Pad1)") (class "Default")
      (node (ref "C17") (pin "1") (pinfunction "1_1") (pintype "passive"))
      (node (ref "R4") (pin "1") (pinfunction "1_1") (pintype "passive"))
    )
    (net (code "71") (name "Net-(JP2-Pad2)") (class "Default")
      (node (ref "JP2") (pin "2") (pinfunction "2_2") (pintype "passive"))
      (node (ref "RN1") (pin "1") (pinfunction "1_1") (pintype "passive"))
    )
    (net (code "72") (name "Net-(LD1-AG)") (class "Default")
      (node (ref "LD1") (pin "AX") (pinfunction "AG_AX") (pintype "passive"))
      (node (ref "U11") (pin "6") (pinfunction "O_6") (pintype "output"))
    )
    (net (code "73") (name "Net-(LD1-PadC)") (class "Default")
      (node (ref "LD1") (pin "C") (pinfunction "C_C") (pintype "passive"))
      (node (ref "R15") (pin "1") (pinfunction "1_1") (pintype "passive"))
    )
    (net (code "74") (name "Net-(Q1-D)") (class "Default")
      (node (ref "JP1") (pin "1") (pinfunction "1_1") (pintype "passive"))
      (node (ref "Q1") (pin "3") (pinfunction "D_3") (pintype "passive"))
    )
    (net (code "75") (name "Net-(Q1-G)") (class "Default")
      (node (ref "Q1") (pin "2") (pinfunction "G_2") (pintype "passive"))
      (node (ref "U7") (pin "6") (pinfunction "~{Q}_6") (pintype "output"))
    )
    (net (code "76") (name "Net-(S1-S)") (class "Default")
      (node (ref "R1") (pin "1") (pinfunction "1_1") (pintype "passive"))
      (node (ref "S1") (pin "1") (pinfunction "S_1") (pintype "passive"))
      (node (ref "S1") (pin "2") (pinfunction "S1_2") (pintype "passive"))
      (node (ref "U4") (pin "2") (pinfunction "~{RESIN}_2") (pintype "input"))
    )
    (net (code "77") (name "Net-(U4-CT)") (class "Default")
      (node (ref "R4") (pin "2") (pinfunction "2_2") (pintype "passive"))
      (node (ref "U4") (pin "3") (pinfunction "CT_3") (pintype "input"))
    )
    (net (code "78") (name "Net-(U4-REF)") (class "Default")
      (node (ref "C18") (pin "1") (pinfunction "1_1") (pintype "passive"))
      (node (ref "U4") (pin "1") (pinfunction "REF_1") (pintype "bidirectional"))
    )
    (net (code "79") (name "Net-(U4-RESET)") (class "Default")
      (node (ref "R3") (pin "2") (pinfunction "2_2") (pintype "passive"))
      (node (ref "U4") (pin "6") (pinfunction "RESET_6") (pintype "open_collector"))
    )
    (net (code "80") (name "Net-(U6A-Y0)") (class "Default")
      (node (ref "U6") (pin "15") (pinfunction "Y0_15") (pintype "output"))
      (node (ref "U8") (pin "1") (pinfunction "I0_1") (pintype "input"))
    )
    (net (code "81") (name "Net-(U6A-Y1)") (class "Default")
      (node (ref "U6") (pin "14") (pinfunction "Y1_14") (pintype "output"))
      (node (ref "U8") (pin "2") (pinfunction "I1_2") (pintype "input"))
    )
    (net (code "82") (name "Net-(U6A-Y2)") (class "Default")
      (node (ref "U6") (pin "13") (pinfunction "Y2_13") (pintype "output"))
      (node (ref "U8") (pin "13") (pinfunction "I2_13") (pintype "input"))
    )
    (net (code "83") (name "Net-(U7A-PRE)") (class "Default")
      (node (ref "U7") (pin "4") (pinfunction "PRE_4") (pintype "input"))
      (node (ref "U7") (pin "9") (pinfunction "Q_9") (pintype "output"))
    )
    (net (code "84") (name "Net-(U7A-Q)") (class "Default")
      (node (ref "U7") (pin "12") (pinfunction "D_12") (pintype "input"))
      (node (ref "U7") (pin "5") (pinfunction "Q_5") (pintype "output"))
    )
    (net (code "85") (name "Net-(U9D-O)") (class "Default")
      (node (ref "LD1") (pin "AR") (pinfunction "AR_AR") (pintype "passive"))
      (node (ref "U9") (pin "13") (pinfunction "O_13") (pintype "output"))
    )
    (net (code "86") (name "Net-(U10A-I1)") (class "Default")
      (node (ref "U10") (pin "2") (pinfunction "I1_2") (pintype "input"))
      (node (ref "U11") (pin "3") (pinfunction "O_3") (pintype "output"))
    )
    (net (code "87") (name "Net-(U10B-O)") (class "Default")
      (node (ref "U10") (pin "6") (pinfunction "O_6") (pintype "output"))
      (node (ref "U8") (pin "5") (pinfunction "I2_5") (pintype "input"))
    )
    (net (code "88") (name "Net-(U10D-I0)") (class "Default")
      (node (ref "U10") (pin "12") (pinfunction "I0_12") (pintype "input"))
      (node (ref "U6") (pin "12") (pinfunction "Y3_12") (pintype "output"))
    )
    (net (code "89") (name "Net-(U10D-I1)") (class "Default")
      (node (ref "U10") (pin "13") (pinfunction "I1_13") (pintype "input"))
      (node (ref "U6") (pin "11") (pinfunction "Y4_11") (pintype "output"))
    )
    (net (code "90") (name "Net-(U11A-I1)") (class "Default")
      (node (ref "U11") (pin "2") (pinfunction "I1_2") (pintype "input"))
      (node (ref "U8") (pin "6") (pinfunction "O_6") (pintype "output"))
    )
    (net (code "91") (name "unconnected-(BUSG-S-Pad15)") (class "Default")
      (node (ref "BUS") (pin "15") (pinfunction "S_15") (pintype "passive"))
    )
    (net (code "92") (name "unconnected-(BUSH-S-Pad16)") (class "Default")
      (node (ref "BUS") (pin "16") (pinfunction "S_16") (pintype "passive"))
    )
    (net (code "93") (name "unconnected-(BUSI-S-Pad17)") (class "Default")
      (node (ref "BUS") (pin "17") (pinfunction "S_17") (pintype "passive"))
    )
    (net (code "94") (name "unconnected-(BUSJ-S-Pad18)") (class "Default")
      (node (ref "BUS") (pin "18") (pinfunction "S_18") (pintype "passive"))
    )
    (net (code "95") (name "unconnected-(BUSK-S-Pad19)") (class "Default")
      (node (ref "BUS") (pin "19") (pinfunction "S_19") (pintype "passive"))
    )
    (net (code "96") (name "unconnected-(BUSM-S-Pad20)") (class "Default")
      (node (ref "BUS") (pin "20") (pinfunction "S_20") (pintype "passive"))
    )
    (net (code "97") (name "unconnected-(BUSN-S-Pad21)") (class "Default")
      (node (ref "BUS") (pin "21") (pinfunction "S_21") (pintype "passive"))
    )
    (net (code "98") (name "unconnected-(BUSO-S-Pad22)") (class "Default")
      (node (ref "BUS") (pin "22") (pinfunction "S_22") (pintype "passive"))
    )
    (net (code "99") (name "unconnected-(J1-Pad2)") (class "Default")
      (node (ref "J1") (pin "2") (pinfunction "2_2") (pintype "passive"))
    )
    (net (code "100") (name "unconnected-(QG1-TS-Pad1)") (class "Default")
      (node (ref "QG1") (pin "1") (pinfunction "TS_1") (pintype "passive"))
    )
    (net (code "101") (name "unconnected-(U3A-A6-Pad7)") (class "Default")
      (node (ref "U3") (pin "7") (pinfunction "A6_7") (pintype "bidirectional"))
    )
    (net (code "102") (name "unconnected-(U3A-A7-Pad8)") (class "Default")
      (node (ref "U3") (pin "8") (pinfunction "A7_8") (pintype "bidirectional"))
    )
    (net (code "103") (name "unconnected-(U5-BUSAK-Pad23)") (class "Default")
      (node (ref "U5") (pin "23") (pinfunction "BUSAK_23") (pintype "output"))
    )
    (net (code "104") (name "unconnected-(U6A-Y5-Pad10)") (class "Default")
      (node (ref "U6") (pin "10") (pinfunction "Y5_10") (pintype "output"))
    )
    (net (code "105") (name "unconnected-(U7B-~{Q}-Pad8)") (class "Default")
      (node (ref "U7") (pin "8") (pinfunction "~{Q}_8") (pintype "output"))
    )
    (net (code "106") (name "unconnected-(U8C-O-Pad8)") (class "Default")
      (node (ref "U8") (pin "8") (pinfunction "O_8") (pintype "output"))
    )
    (net (code "107") (name "unconnected-(U9A-O-Pad1)") (class "Default")
      (node (ref "U9") (pin "1") (pinfunction "O_1") (pintype "output"))
    )
    (net (code "108") (name "unconnected-(U9B-O-Pad4)") (class "Default")
      (node (ref "U9") (pin "4") (pinfunction "O_4") (pintype "output"))
    )
    (net (code "109") (name "unconnected-(U9C-O-Pad10)") (class "Default")
      (node (ref "U9") (pin "10") (pinfunction "O_10") (pintype "output"))
    )
    (net (code "110") (name "unconnected-(U10C-O-Pad8)") (class "Default")
      (node (ref "U10") (pin "8") (pinfunction "O_8") (pintype "output"))
    )
    (net (code "111") (name "unconnected-(U11C-O-Pad8)") (class "Default")
      (node (ref "U11") (pin "8") (pinfunction "O_8") (pintype "output"))
    )
    (net (code "112") (name "unconnected-(U11D-O-Pad11)") (class "Default")
      (node (ref "U11") (pin "11") (pinfunction "O_11") (pintype "output"))
    )
    (net (code "113") (name "~{APP_ROM_CS}") (class "Default")
      (node (ref "U12") (pin "22") (pinfunction "~{CE}_22") (pintype "input"))
      (node (ref "U7") (pin "2") (pinfunction "D_2") (pintype "input"))
      (node (ref "U8") (pin "12") (pinfunction "O_12") (pintype "output"))
      (node (ref "U8") (pin "3") (pinfunction "I0_3") (pintype "input"))
    )
    (net (code "114") (name "~{BUSRQ}") (class "Default")
      (node (ref "R14") (pin "2") (pinfunction "2_2") (pintype "passive"))
      (node (ref "U5") (pin "25") (pinfunction "BUSRQ_25") (pintype "input"))
    )
    (net (code "115") (name "~{CHAR_ROM_CS}") (class "Default")
      (node (ref "U10") (pin "5") (pinfunction "I1_5") (pintype "input"))
      (node (ref "U15") (pin "22") (pinfunction "~{CE}_22") (pintype "input"))
      (node (ref "U6") (pin "7") (pinfunction "Y7_7") (pintype "output"))
    )
    (net (code "116") (name "~{HALT}") (class "Default")
      (node (ref "U11") (pin "4") (pinfunction "I0_4") (pintype "input"))
      (node (ref "U11") (pin "5") (pinfunction "I1_5") (pintype "input"))
      (node (ref "U5") (pin "18") (pinfunction "HALT_18") (pintype "output"))
      (node (ref "U9") (pin "11") (pinfunction "I0_11") (pintype "input"))
      (node (ref "U9") (pin "12") (pinfunction "I1_12") (pintype "input"))
    )
    (net (code "117") (name "~{INT}") (class "Default")
      (node (ref "BUS") (pin "11") (pinfunction "S_11") (pintype "passive"))
      (node (ref "R12") (pin "2") (pinfunction "2_2") (pintype "passive"))
      (node (ref "U5") (pin "16") (pinfunction "INT_16") (pintype "input"))
    )
    (net (code "118") (name "~{IORQ}") (class "Default")
      (node (ref "R7") (pin "2") (pinfunction "2_2") (pintype "passive"))
      (node (ref "U3") (pin "16") (pinfunction "B3_16") (pintype "bidirectional"))
      (node (ref "U5") (pin "20") (pinfunction "IORQ_20") (pintype "output"))
    )
    (net (code "119") (name "~{M1}") (class "Default")
      (node (ref "R5") (pin "2") (pinfunction "2_2") (pintype "passive"))
      (node (ref "U3") (pin "18") (pinfunction "B1_18") (pintype "bidirectional"))
      (node (ref "U5") (pin "27") (pinfunction "M1_27") (pintype "output"))
    )
    (net (code "120") (name "~{MREQ}") (class "Default")
      (node (ref "R6") (pin "2") (pinfunction "2_2") (pintype "passive"))
      (node (ref "U3") (pin "17") (pinfunction "B2_17") (pintype "bidirectional"))
      (node (ref "U5") (pin "19") (pinfunction "MREQ_19") (pintype "output"))
      (node (ref "U6") (pin "4") (pinfunction "G2A_4") (pintype "input"))
    )
    (net (code "121") (name "~{NMI}") (class "Default")
      (node (ref "BUS") (pin "12") (pinfunction "S_12") (pintype "passive"))
      (node (ref "R13") (pin "2") (pinfunction "2_2") (pintype "passive"))
      (node (ref "U5") (pin "17") (pinfunction "NMI_17") (pintype "input"))
    )
    (net (code "122") (name "~{RAM_CS}") (class "Default")
      (node (ref "U10") (pin "11") (pinfunction "O_11") (pintype "output"))
      (node (ref "U13") (pin "20") (pinfunction "~{CE}_20") (pintype "input"))
      (node (ref "U8") (pin "4") (pinfunction "I1_4") (pintype "input"))
    )
    (net (code "123") (name "~{RD}") (class "Default")
      (node (ref "R8") (pin "2") (pinfunction "2_2") (pintype "passive"))
      (node (ref "U11") (pin "1") (pinfunction "I0_1") (pintype "input"))
      (node (ref "U12") (pin "24") (pinfunction "~{OE}_24") (pintype "input"))
      (node (ref "U13") (pin "22") (pinfunction "~{OE}_22") (pintype "input"))
      (node (ref "U14") (pin "24") (pinfunction "~{OE}_24") (pintype "input"))
      (node (ref "U15") (pin "24") (pinfunction "~{OE}_24") (pintype "input"))
      (node (ref "U3") (pin "15") (pinfunction "B4_15") (pintype "bidirectional"))
      (node (ref "U5") (pin "21") (pinfunction "RD_21") (pintype "output"))
    )
    (net (code "124") (name "~{RESET}") (class "Default")
      (node (ref "BUS") (pin "6") (pinfunction "S_6") (pintype "passive"))
      (node (ref "R2") (pin "2") (pinfunction "2_2") (pintype "passive"))
      (node (ref "U4") (pin "5") (pinfunction "~{RESET}_5") (pintype "open_collector"))
      (node (ref "U5") (pin "26") (pinfunction "RESET_26") (pintype "input"))
    )
    (net (code "125") (name "~{RFSH}") (class "Default")
      (node (ref "R10") (pin "2") (pinfunction "2_2") (pintype "passive"))
      (node (ref "U5") (pin "28") (pinfunction "RFSH_28") (pintype "output"))
      (node (ref "U6") (pin "6") (pinfunction "G1_6") (pintype "input"))
    )
    (net (code "126") (name "~{TZ_ROM_CS}") (class "Default")
      (node (ref "U10") (pin "4") (pinfunction "I0_4") (pintype "input"))
      (node (ref "U14") (pin "22") (pinfunction "~{CE}_22") (pintype "input"))
      (node (ref "U6") (pin "9") (pinfunction "Y6_9") (pintype "output"))
    )
    (net (code "127") (name "~{WAIT}") (class "Default")
      (node (ref "BUS") (pin "10") (pinfunction "S_10") (pintype "passive"))
      (node (ref "JP1") (pin "2") (pinfunction "2_2") (pintype "passive"))
      (node (ref "R11") (pin "2") (pinfunction "2_2") (pintype "passive"))
      (node (ref "U5") (pin "24") (pinfunction "WAIT_24") (pintype "input"))
    )
    (net (code "128") (name "~{WR}") (class "Default")
      (node (ref "R9") (pin "2") (pinfunction "2_2") (pintype "passive"))
      (node (ref "U10") (pin "1") (pinfunction "I0_1") (pintype "input"))
      (node (ref "U12") (pin "31") (pinfunction "~{WE}_31") (pintype "input"))
      (node (ref "U13") (pin "27") (pinfunction "~{WE}_27") (pintype "input"))
      (node (ref "U14") (pin "31") (pinfunction "~{WE}_31") (pintype "input"))
      (node (ref "U15") (pin "31") (pinfunction "~{WE}_31") (pintype "input"))
      (node (ref "U3") (pin "14") (pinfunction "B5_14") (pintype "bidirectional"))
      (node (ref "U5") (pin "22") (pinfunction "WR_22") (pintype "output"))
    )
  )
)
